# Carrier_Board.net
KiCad netlist of a schematic drawn in EAGLE
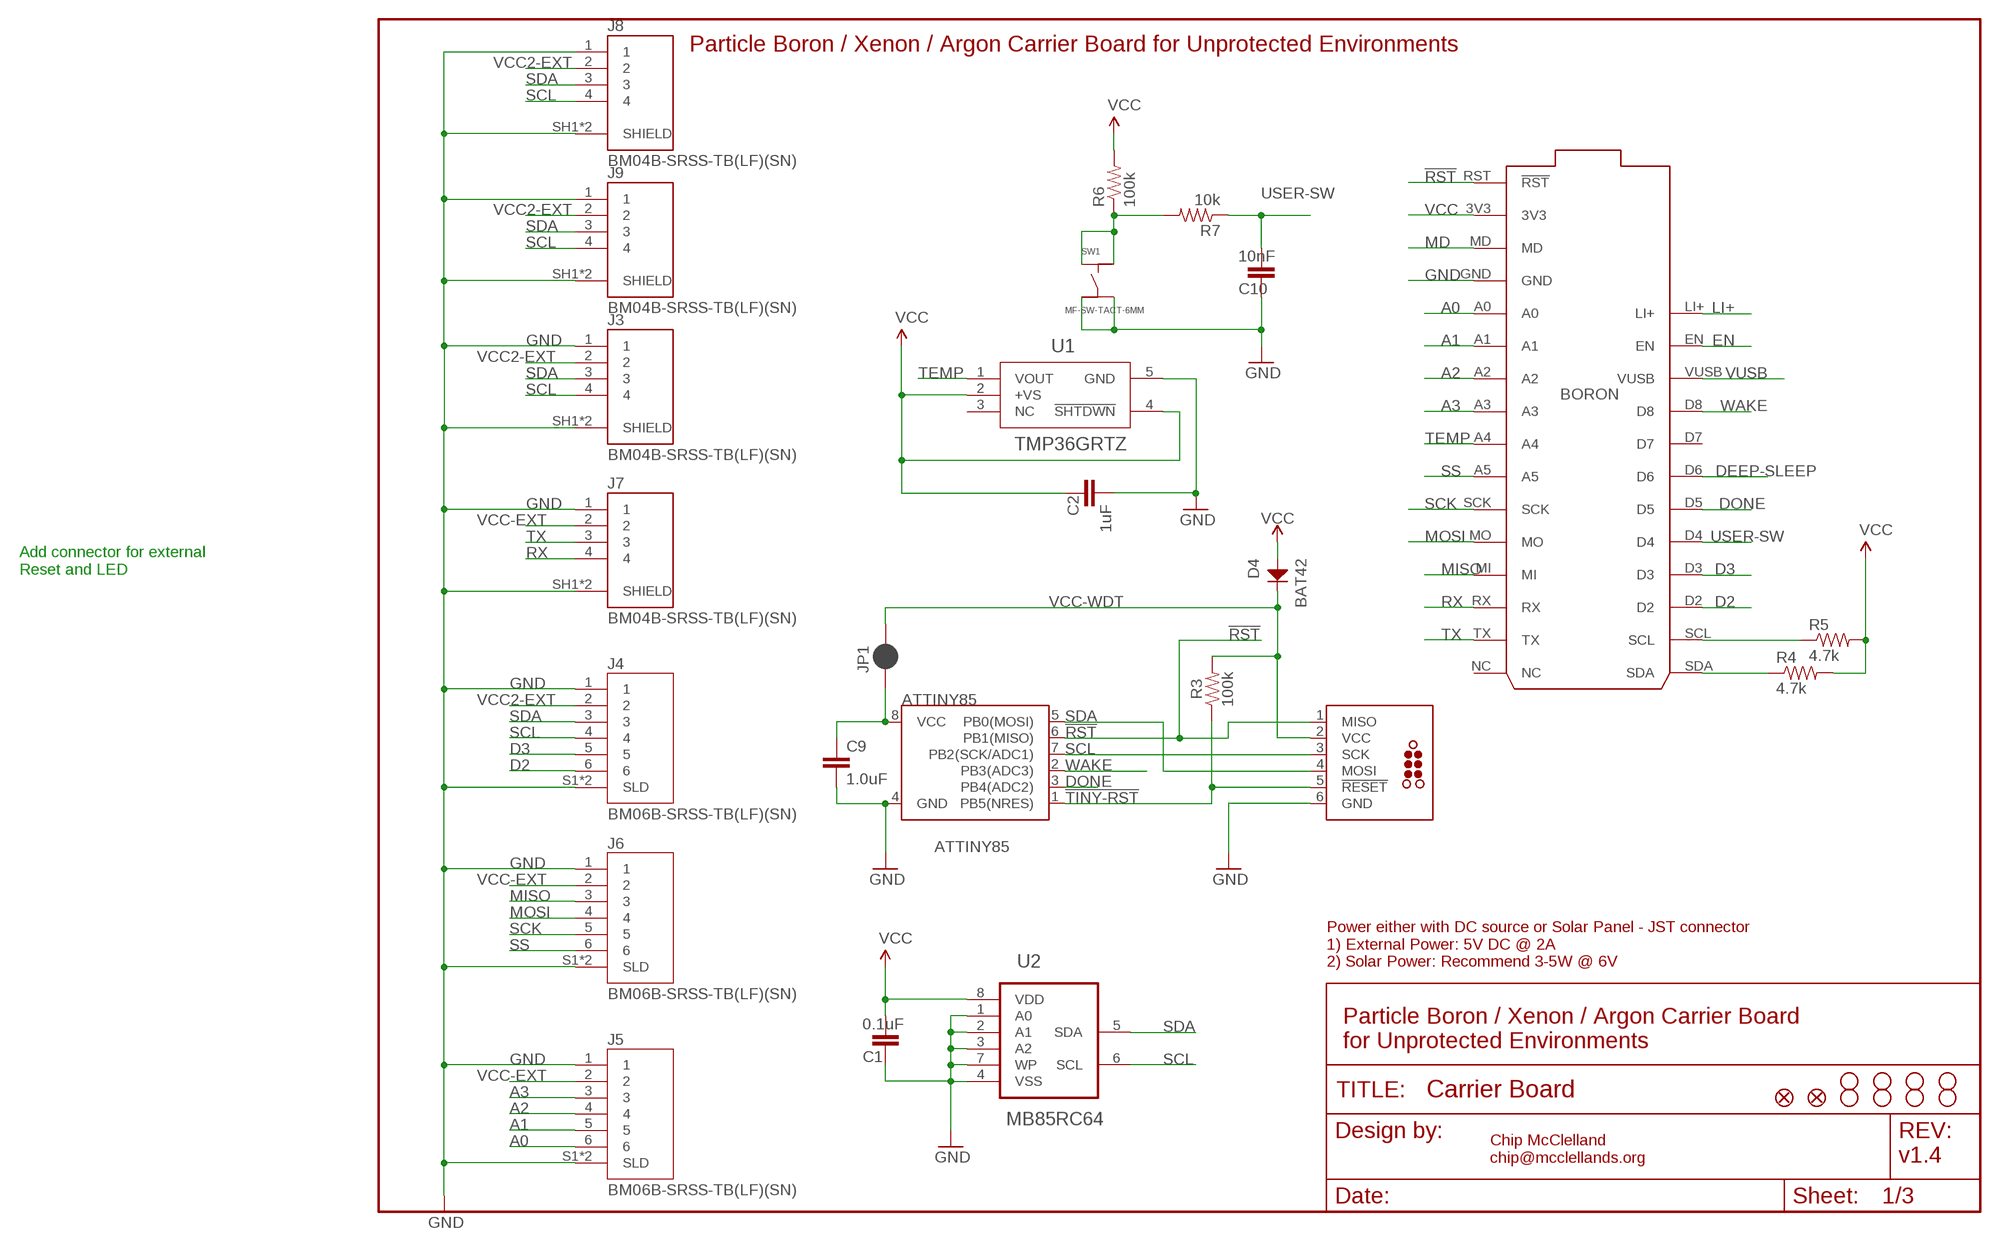
[diagram p0: schematic, sheet 1]
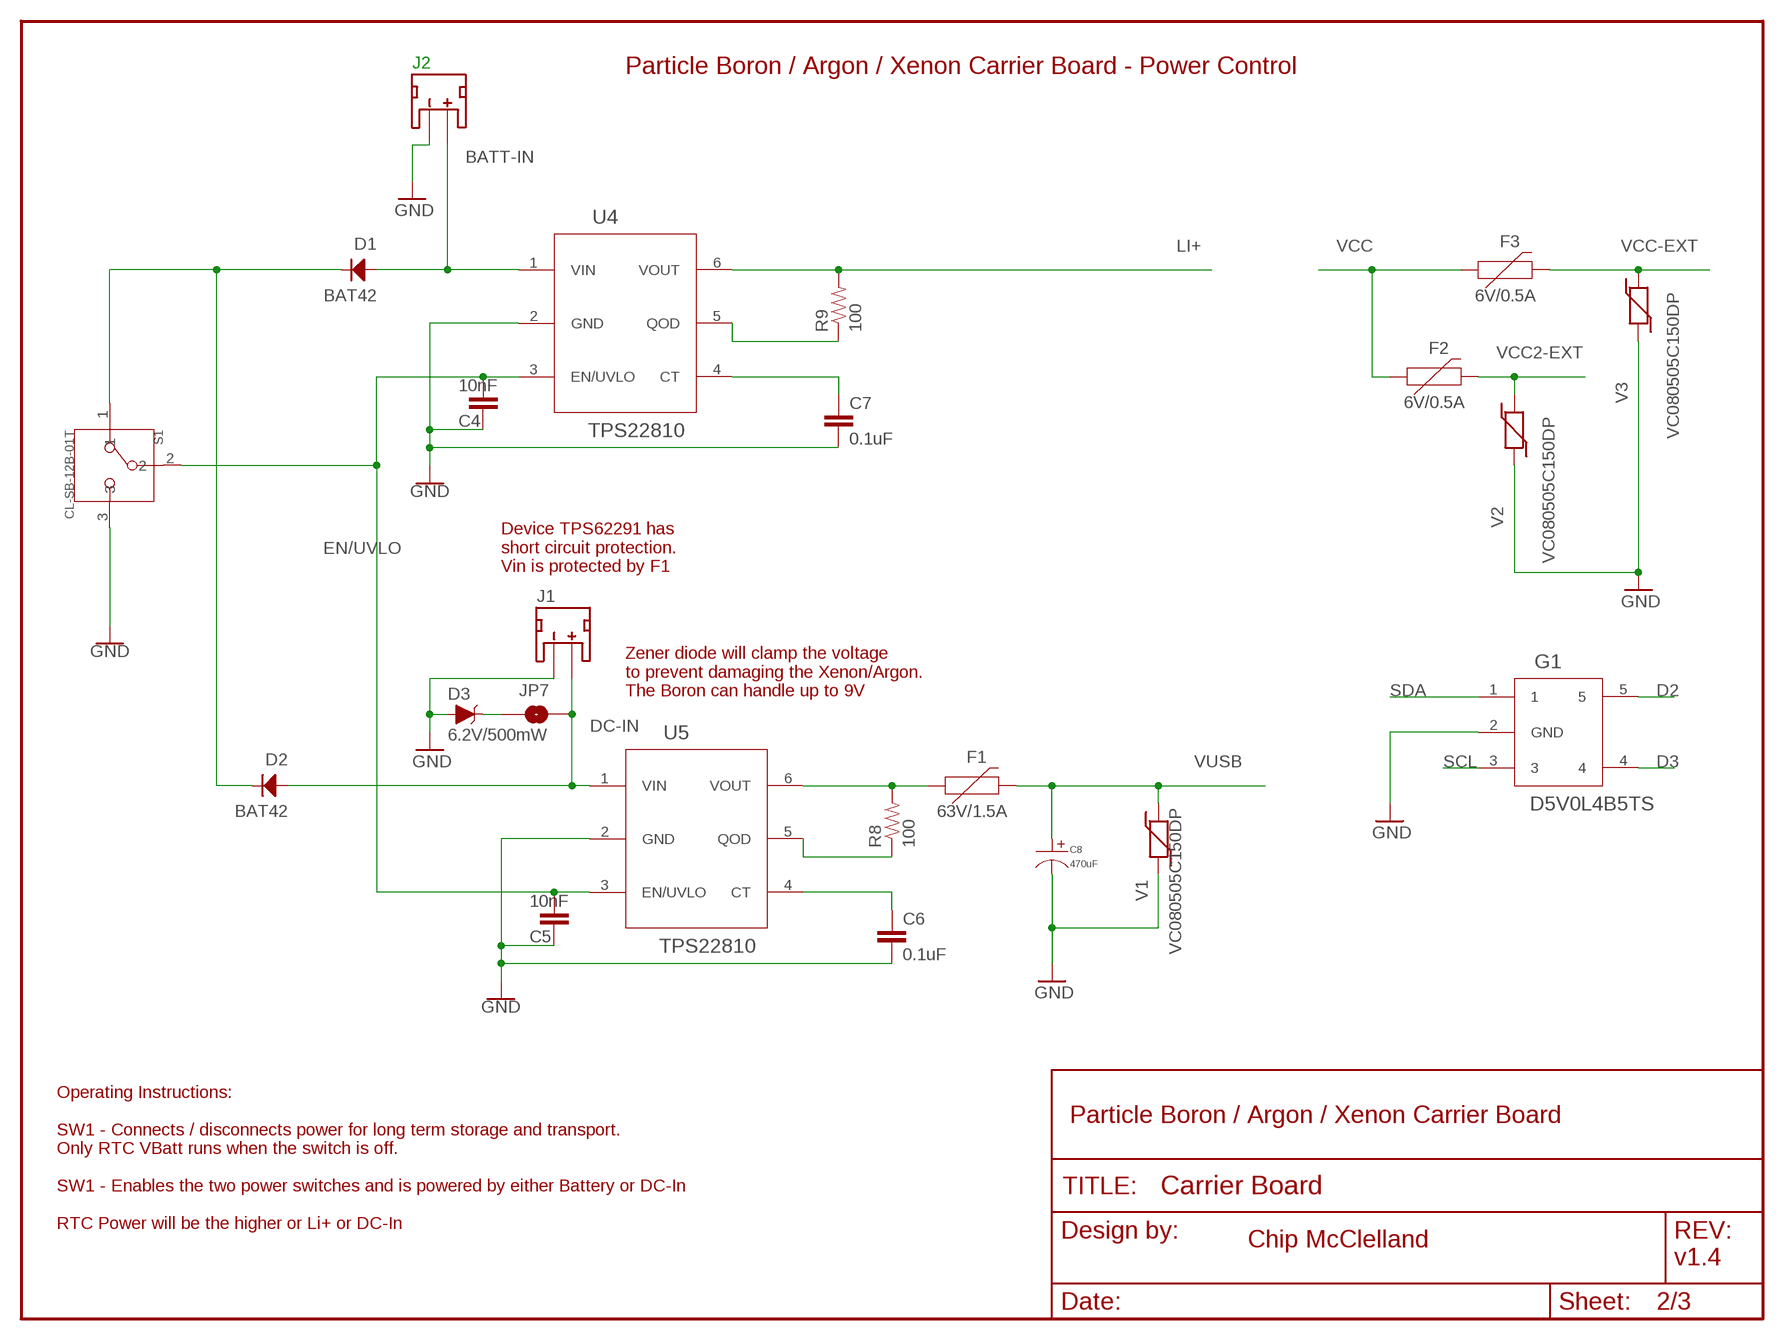
[diagram p1: schematic, sheet 2]
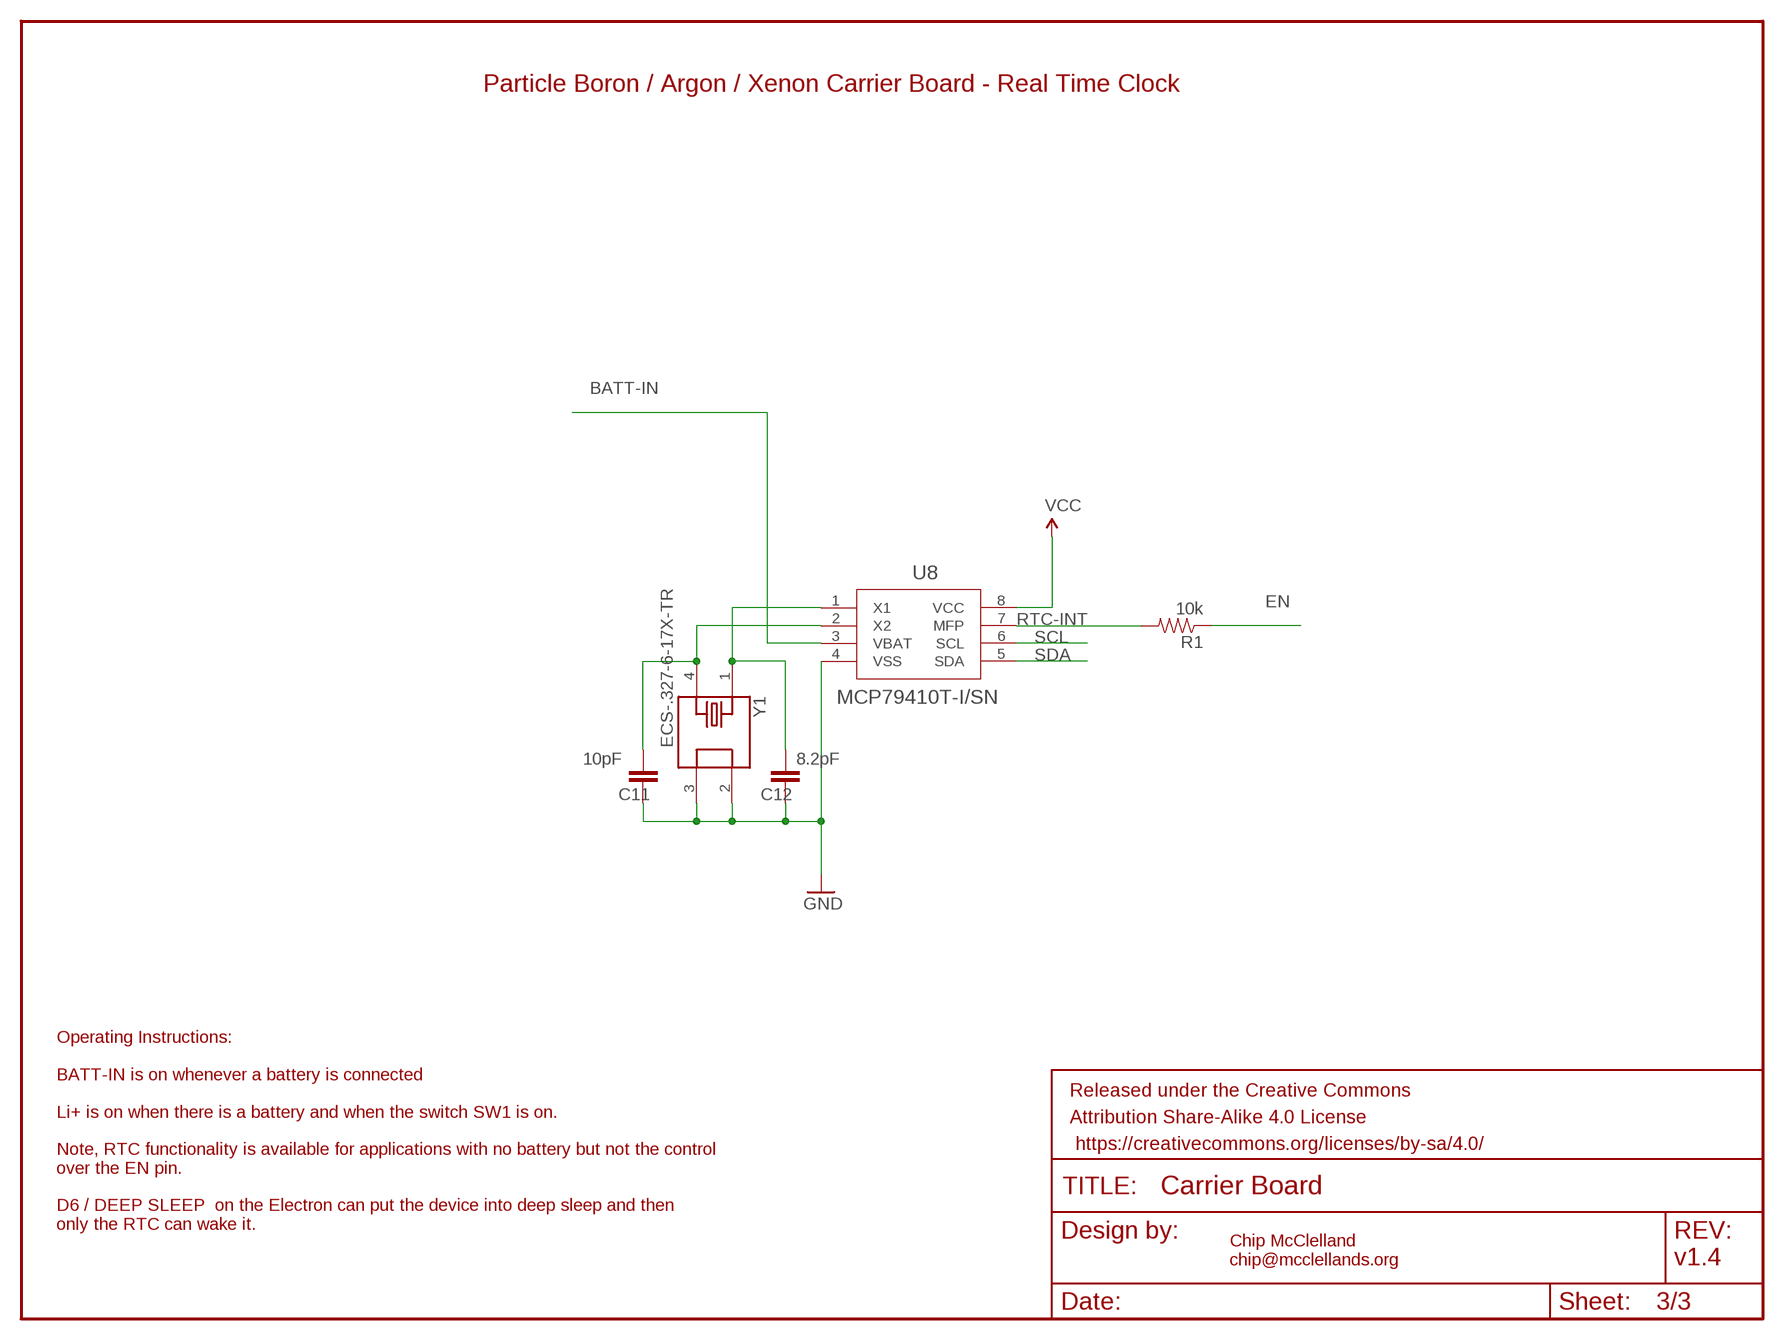
[diagram p2: schematic, sheet 3]

(export (version "E")
  (design (tool "Eeschema 10.0.6"))
  (components
    (comp (ref "ATTINY85")
      (value "ATTINY85")
      (footprint "eagle-import:SO08-EIAJ")
      (fields (field (name "MPN") "ATTINY85-20SUR"))
      (libsource (lib "eagle-import") (part "ATTINY45"))
    )
    (comp (ref "C1")
      (value "0.1uF")
      (footprint "eagle-import:0805@1")
      (fields (field (name "HOUSEPART") "YES") (field (name "MPN") "MF-CAP-0805-0.1uF"))
      (libsource (lib "eagle-import") (part "CAP0805"))
    )
    (comp (ref "C2")
      (value "1uF")
      (footprint "eagle-import:0805@1")
      (fields (field (name "MPN") "MF-CAP-0805-1uF"))
      (libsource (lib "eagle-import") (part "CAP0805"))
    )
    (comp (ref "C9")
      (value "1.0uF")
      (footprint "eagle-import:0805")
      (fields (field (name "MPN") "MF-CAP-0805-0.1uF"))
      (libsource (lib "eagle-import") (part "1.0UF-0805-25V-10%"))
    )
    (comp (ref "C10")
      (value "10nF")
      (footprint "eagle-import:0805@1")
      (fields (field (name "HOUSEPART") "No") (field (name "MPN") "08051C103K4T2A"))
      (libsource (lib "eagle-import") (part "CAP0805"))
    )
    (comp (ref "D4")
      (value "BAT42")
      (footprint "eagle-import:SOD-123")
      (fields (field (name "HOUSEPART") "YES") (field (name "MPN") "MF-DIO-SOD123-BAT42"))
      (libsource (lib "eagle-import") (part "DIODES_SOD-123_BAT42"))
    )
    (comp (ref "FD1")
      (value "FIDUCIALUFIDUCIAL")
      (footprint "eagle-import:FIDUCIAL-MICRO")
      (libsource (lib "eagle-import") (part "FIDUCIALUFIDUCIAL"))
    )
    (comp (ref "FD2")
      (value "FIDUCIALUFIDUCIAL")
      (footprint "eagle-import:FIDUCIAL-MICRO")
      (libsource (lib "eagle-import") (part "FIDUCIALUFIDUCIAL"))
    )
    (comp (ref "FRAME1")
      (value "FRAME-LETTER")
      (footprint "eagle-import:CREATIVE_COMMONS")
      (fields (field (name "POPULATE") "0"))
      (libsource (lib "eagle-import") (part "FRAME-LETTER"))
    )
    (comp (ref "H1")
      (value "STAND-OFF-M2.5")
      (footprint "eagle-import:STAND-OFF-M2.5")
      (libsource (lib "eagle-import") (part "STAND-OFF-M2.5"))
    )
    (comp (ref "H2")
      (value "STAND-OFF-M2.5")
      (footprint "eagle-import:STAND-OFF-M2.5")
      (libsource (lib "eagle-import") (part "STAND-OFF-M2.5"))
    )
    (comp (ref "H3")
      (value "STAND-OFF-M2.5")
      (footprint "eagle-import:STAND-OFF-M2.5")
      (libsource (lib "eagle-import") (part "STAND-OFF-M2.5"))
    )
    (comp (ref "H4")
      (value "STAND-OFF-M2.5")
      (footprint "eagle-import:STAND-OFF-M2.5")
      (libsource (lib "eagle-import") (part "STAND-OFF-M2.5"))
    )
    (comp (ref "ICSP")
      (value "TCP2030-MCP-NL")
      (footprint "eagle-import:TC2030-MCP-NL")
      (libsource (lib "eagle-import") (part "TCP2030-MCP-NL"))
    )
    (comp (ref "J3")
      (value "BM04B-SRSS-TB(LF)(SN)")
      (footprint "eagle-import:CONN_BM04B-SRSS-TBT(LF)(SN)")
      (fields (field (name "MF") "JST Sales") (field (name "MP") "BM04B-SRSS-TB_LF__SN_"))
      (libsource (lib "eagle-import") (part "BM04B-SRSS-TBT(LF)(SN)"))
    )
    (comp (ref "J4")
      (value "BM06B-SRSS-TB(LF)(SN)")
      (footprint "eagle-import:JST_BM06B-SRSS-TB(LF)(SN)")
      (libsource (lib "eagle-import") (part "BM06B-SRSS-TB(LF)(SN)"))
    )
    (comp (ref "J5")
      (value "BM06B-SRSS-TB(LF)(SN)")
      (footprint "eagle-import:JST_BM06B-SRSS-TB(LF)(SN)")
      (libsource (lib "eagle-import") (part "BM06B-SRSS-TB(LF)(SN)"))
    )
    (comp (ref "J6")
      (value "BM06B-SRSS-TB(LF)(SN)")
      (footprint "eagle-import:JST_BM06B-SRSS-TB(LF)(SN)")
      (libsource (lib "eagle-import") (part "BM06B-SRSS-TB(LF)(SN)"))
    )
    (comp (ref "J7")
      (value "BM04B-SRSS-TB(LF)(SN)")
      (footprint "eagle-import:CONN_BM04B-SRSS-TBT(LF)(SN)")
      (fields (field (name "MF") "JST Sales") (field (name "MP") "BM04B-SRSS-TB_LF__SN_"))
      (libsource (lib "eagle-import") (part "BM04B-SRSS-TBT(LF)(SN)"))
    )
    (comp (ref "J8")
      (value "BM04B-SRSS-TB(LF)(SN)")
      (footprint "eagle-import:CONN_BM04B-SRSS-TBT(LF)(SN)")
      (fields (field (name "MF") "JST Sales") (field (name "MP") "BM04B-SRSS-TB_LF__SN_"))
      (libsource (lib "eagle-import") (part "BM04B-SRSS-TBT(LF)(SN)"))
    )
    (comp (ref "J9")
      (value "BM04B-SRSS-TB(LF)(SN)")
      (footprint "eagle-import:CONN_BM04B-SRSS-TBT(LF)(SN)")
      (fields (field (name "MF") "JST Sales") (field (name "MP") "BM04B-SRSS-TB_LF__SN_"))
      (libsource (lib "eagle-import") (part "BM04B-SRSS-TBT(LF)(SN)"))
    )
    (comp (ref "JP1")
      (value "JUMPER-SMT_2_NC_PASTE_SILK")
      (footprint "eagle-import:SMT-JUMPER_2_NC_PASTE_SILK")
      (libsource (lib "eagle-import") (part "JUMPER-SMT_2_NC_PASTE_SILK"))
    )
    (comp (ref "JP3")
      (value "STAND-OFF")
      (footprint "eagle-import:STAND-OFF")
      (libsource (lib "eagle-import") (part "STAND-OFF"))
    )
    (comp (ref "JP4")
      (value "STAND-OFF")
      (footprint "eagle-import:STAND-OFF")
      (libsource (lib "eagle-import") (part "STAND-OFF"))
    )
    (comp (ref "JP5")
      (value "STAND-OFF")
      (footprint "eagle-import:STAND-OFF")
      (libsource (lib "eagle-import") (part "STAND-OFF"))
    )
    (comp (ref "JP6")
      (value "STAND-OFF")
      (footprint "eagle-import:STAND-OFF")
      (libsource (lib "eagle-import") (part "STAND-OFF"))
    )
    (comp (ref "P1")
      (value "Particle Boron / Xenon / Argon")
      (footprint "eagle-import:PARTICLE-DEVICES_BORON")
      (libsource (lib "eagle-import") (part "PARTICLE-DEVICES-BORON"))
    )
    (comp (ref "R3")
      (value "100k")
      (footprint "eagle-import:0805")
      (fields (field (name "MPN") "MF-RES-0805-100K"))
      (libsource (lib "eagle-import") (part "0.3OHM-0805-1/8W-1%"))
    )
    (comp (ref "R4")
      (value "4.7k")
      (footprint "eagle-import:0805")
      (fields (field (name "MPN") "MF-RES-0805-4.7K"))
      (libsource (lib "eagle-import") (part "RESISTOR0805-RES"))
    )
    (comp (ref "R5")
      (value "4.7k")
      (footprint "eagle-import:0805")
      (fields (field (name "MPN") "MF-RES-0805-4.7K"))
      (libsource (lib "eagle-import") (part "RESISTOR0805-RES"))
    )
    (comp (ref "R6")
      (value "100k")
      (footprint "eagle-import:0805")
      (fields (field (name "HOUSEPART") "YES") (field (name "MPN") "MF-RES-0805-100K"))
      (libsource (lib "eagle-import") (part "RESISTOR0805-RES"))
    )
    (comp (ref "R7")
      (value "10k")
      (footprint "eagle-import:0805")
      (fields (field (name "HOUSEPART") "YES") (field (name "MPN") "MF-RES-0805-10K"))
      (libsource (lib "eagle-import") (part "RESISTOR0805-RES"))
    )
    (comp (ref "SW1")
      (value "MF-SW-TACT-6MM")
      (footprint "eagle-import:TACT6MM")
      (fields (field (name "HOUSEPART") "YES"))
      (libsource (lib "eagle-import") (part "TACT_6MM"))
    )
    (comp (ref "U1")
      (value "TMP36GRTZ")
      (footprint "eagle-import:RJ_5")
      (fields
        (field (name "MANUFACTURER_PART_NUMBER") "TMP36GRTZREEL7")
        (field (name "MANUFACTURER_PART_NUMBER_1") "TMP36GRTZ-REEL7")
        (field (name "MPN") "TMP36GRTZ-REEL7")
      )
      (libsource (lib "eagle-import") (part "TMP36GRTZ-REEL7"))
    )
    (comp (ref "U2")
      (value "MB85RC64")
      (footprint "eagle-import:SOIC127P600X175-8N")
      (fields (field (name "MPN") "MB85RC128PNF-G-JNE1") (field (name "MPN_1") "MB85RC64APNF-G-JNERE1"))
      (libsource (lib "eagle-import") (part "MB85RC128PNF-G-JNE1"))
    )
    (comp (ref "C11")
      (value "10pF")
      (footprint "eagle-import:0805@1")
      (fields (field (name "HOUSEPART") "No") (field (name "MPN") "C0805C100JDGACTU‎"))
      (libsource (lib "eagle-import") (part "CAP0805"))
    )
    (comp (ref "C12")
      (value "8.2pF")
      (footprint "eagle-import:0805@1")
      (fields (field (name "HOUSEPART") "No") (field (name "MPN") "C0805C829D5GACTU‎"))
      (libsource (lib "eagle-import") (part "CAP0805"))
    )
    (comp (ref "FRAME3")
      (value "FRAME-LETTER")
      (footprint "eagle-import:CREATIVE_COMMONS")
      (fields (field (name "POPULATE") "0"))
      (libsource (lib "eagle-import") (part "SparkFun-Aesthetics_507_FRAME-LETTER"))
    )
    (comp (ref "R1")
      (value "10k")
      (footprint "eagle-import:0805")
      (fields (field (name "HOUSEPART") "YES") (field (name "MPN") "MF-RES-0805-10K"))
      (libsource (lib "eagle-import") (part "RESISTOR0805-RES"))
    )
    (comp (ref "U8")
      (value "MCP79410T-I/SN")
      (footprint "eagle-import:SOIC8-N_MC")
      (fields (field (name "MANUFACTURER_PART_NUMBER") "MCP79410TISN"))
      (libsource (lib "eagle-import") (part "MCP79410T-I/SN"))
    )
    (comp (ref "Y1")
      (value "ECS-.327-6-17X-TR")
      (footprint "eagle-import:XTAL_ECS-.327-6-17X-TR")
      (fields (field (name "DIGI-KEY_PART_NUMBER") "XC1307CT-ND") (field (name "MF") "ECS Inc."))
      (libsource (lib "eagle-import") (part "ECS-.327-6-17X-TR"))
    )
    (comp (ref "C4")
      (value "10nF")
      (footprint "eagle-import:0805@1")
      (fields (field (name "HOUSEPART") "No") (field (name "MPN") "08051C103K4T2A"))
      (libsource (lib "eagle-import") (part "CAP0805"))
    )
    (comp (ref "C5")
      (value "10nF")
      (footprint "eagle-import:0805@1")
      (fields (field (name "HOUSEPART") "No") (field (name "MPN") "08051C103K4T2A"))
      (libsource (lib "eagle-import") (part "CAP0805"))
    )
    (comp (ref "C6")
      (value "0.1uF")
      (footprint "eagle-import:0805@1")
      (fields (field (name "HOUSEPART") "Yes") (field (name "MPN") "MF-CAP-0805-0.1uF"))
      (libsource (lib "eagle-import") (part "CAP0805"))
    )
    (comp (ref "C7")
      (value "0.1uF")
      (footprint "eagle-import:0805@1")
      (fields (field (name "HOUSEPART") "Yes") (field (name "MPN") "MF-CAP-0805-0.1uF"))
      (libsource (lib "eagle-import") (part "CAP0805"))
    )
    (comp (ref "C8")
      (value "470uF")
      (footprint "eagle-import:CP10MM")
      (fields (field (name "HOUSEPART") "1") (field (name "MPN") "MF-CAP-10MM-470uF"))
      (libsource (lib "eagle-import") (part "CAPACITOR_P_10MM"))
    )
    (comp (ref "D1")
      (value "BAT42")
      (footprint "eagle-import:SOD-123")
      (fields (field (name "HOUSEPART") "YES") (field (name "MPN") "MF-DIO-SOD123-BAT42"))
      (libsource (lib "eagle-import") (part "DIODES_SOD-123_BAT42"))
    )
    (comp (ref "D2")
      (value "BAT42")
      (footprint "eagle-import:SOD-123")
      (fields (field (name "HOUSEPART") "YES") (field (name "MPN") "MF-DIO-SOD123-BAT42"))
      (libsource (lib "eagle-import") (part "DIODES_SOD-123_BAT42"))
    )
    (comp (ref "D3")
      (value "6.2V/500mW")
      (footprint "eagle-import:PANASONIC_SMINI2-F5-B")
      (fields (field (name "MPN") "TDZ6V2J,115"))
      (libsource (lib "eagle-import") (part "DIODE-ZENER-DZ2J150M0L"))
    )
    (comp (ref "F1")
      (value "63V/1.5A")
      (footprint "eagle-import:1206")
      (fields (field (name "MPN") "046801.5NR"))
      (libsource (lib "eagle-import") (part "PPTC_HALF-AMP"))
    )
    (comp (ref "F2")
      (value "6V/0.5A")
      (footprint "eagle-import:1206")
      (fields (field (name "MPN") "0466.500NR"))
      (libsource (lib "eagle-import") (part "PPTC_HALF-AMP"))
    )
    (comp (ref "F3")
      (value "6V/0.5A")
      (footprint "eagle-import:1206")
      (fields (field (name "MPN") "0466.500NR"))
      (libsource (lib "eagle-import") (part "PPTC_HALF-AMP"))
    )
    (comp (ref "FRAME2")
      (value "FRAME-LETTER")
      (footprint "eagle-import:CREATIVE_COMMONS")
      (fields (field (name "POPULATE") "0"))
      (libsource (lib "eagle-import") (part "FRAME-LETTER"))
    )
    (comp (ref "G1")
      (value "D5V0L4B5TS")
      (footprint "eagle-import:SOT-23-5")
      (fields (field (name "MPN") "D5V0L4B5TS-7"))
      (libsource (lib "eagle-import") (part "D5V0L4B5TS"))
    )
    (comp (ref "J1")
      (value "S2B-PH-SM4-TB(LF)(SN)")
      (footprint "eagle-import:JST-2-SMD")
      (fields (field (name "MFG") "JST S2B-PH-SM4-TB(LF)(SN)"))
      (libsource (lib "eagle-import") (part "JST_2MM_MALE"))
    )
    (comp (ref "J2")
      (value "S2B-PH-SM4-TB(LF)(SN)")
      (footprint "eagle-import:JST-2-SMD")
      (fields (field (name "MFG") "JST S2B-PH-SM4-TB(LF)(SN)"))
      (libsource (lib "eagle-import") (part "JST_2MM_MALE"))
    )
    (comp (ref "JP7")
      (value "JUMPER-SMT_2_NO_SILK")
      (footprint "eagle-import:SMT-JUMPER_2_NO_SILK")
      (libsource (lib "eagle-import") (part "JUMPER-SMT_2_NO_SILK"))
    )
    (comp (ref "R8")
      (value "100")
      (footprint "eagle-import:0805")
      (fields (field (name "HOUSEPART") "Yes") (field (name "MPN") "MF-RES-0805-100"))
      (libsource (lib "eagle-import") (part "RESISTOR0805-RES"))
    )
    (comp (ref "R9")
      (value "100")
      (footprint "eagle-import:0805")
      (fields (field (name "HOUSEPART") "Yes") (field (name "MPN") "MF-RES-0805-100"))
      (libsource (lib "eagle-import") (part "RESISTOR0805-RES"))
    )
    (comp (ref "S1")
      (value "CL-SB-12B-01T")
      (footprint "eagle-import:CL-SB-12B")
      (fields (field (name "DIGI-KEY_PART_NUMBER") "563-1318-1-ND") (field (name "MF") "Nidec Copal"))
      (libsource (lib "eagle-import") (part "CL-SB-12B-01T"))
    )
    (comp (ref "U4")
      (value "TPS22810")
      (footprint "eagle-import:SOT-23-6")
      (fields (field (name "MPN") "TPS22810DBVT"))
      (libsource (lib "eagle-import") (part "TPS22810"))
    )
    (comp (ref "U5")
      (value "TPS22810")
      (footprint "eagle-import:SOT-23-6")
      (fields (field (name "MPN") "TPS22810DBVT"))
      (libsource (lib "eagle-import") (part "TPS22810"))
    )
    (comp (ref "V1")
      (value "VC080505C150DP")
      (footprint "eagle-import:0805")
      (libsource (lib "eagle-import") (part "VARISTOR"))
    )
    (comp (ref "V2")
      (value "VC080505C150DP")
      (footprint "eagle-import:0805")
      (libsource (lib "eagle-import") (part "VARISTOR"))
    )
    (comp (ref "V3")
      (value "VC080505C150DP")
      (footprint "eagle-import:0805")
      (libsource (lib "eagle-import") (part "VARISTOR"))
    )
  )
  (nets
    (net (code "1") (name "A0") (class "Default")
      (node (ref "J5") (pin "6") (pinfunction "6_6") (pintype "passive"))
      (node (ref "P1") (pin "A0") (pinfunction "A0_A0") (pintype "bidirectional"))
    )
    (net (code "2") (name "A1") (class "Default")
      (node (ref "J5") (pin "5") (pinfunction "5_5") (pintype "passive"))
      (node (ref "P1") (pin "A1") (pinfunction "A1_A1") (pintype "bidirectional"))
    )
    (net (code "3") (name "A2") (class "Default")
      (node (ref "J5") (pin "4") (pinfunction "4_4") (pintype "passive"))
      (node (ref "P1") (pin "A2") (pinfunction "A2_A2") (pintype "bidirectional"))
    )
    (net (code "4") (name "A3") (class "Default")
      (node (ref "J5") (pin "3") (pinfunction "3_3") (pintype "passive"))
      (node (ref "P1") (pin "A3") (pinfunction "A3_A3") (pintype "bidirectional"))
    )
    (net (code "5") (name "BATT-IN") (class "Default")
      (node (ref "D1") (pin "ANODE") (pinfunction "ANODE_ANODE") (pintype "bidirectional"))
      (node (ref "J2") (pin "2") (pinfunction "+_2") (pintype "bidirectional"))
      (node (ref "U4") (pin "1") (pinfunction "VIN_1") (pintype "power_in"))
      (node (ref "U8") (pin "3") (pinfunction "VBAT_3") (pintype "input"))
    )
    (net (code "6") (name "D2") (class "Default")
      (node (ref "G1") (pin "5") (pinfunction "5_5") (pintype "output"))
      (node (ref "J4") (pin "6") (pinfunction "6_6") (pintype "passive"))
      (node (ref "P1") (pin "D2") (pinfunction "D2_D2") (pintype "bidirectional"))
    )
    (net (code "7") (name "D3") (class "Default")
      (node (ref "G1") (pin "4") (pinfunction "4_4") (pintype "output"))
      (node (ref "J4") (pin "5") (pinfunction "5_5") (pintype "passive"))
      (node (ref "P1") (pin "D3") (pinfunction "D3_D3") (pintype "bidirectional"))
    )
    (net (code "8") (name "DC-IN") (class "Default")
      (node (ref "D2") (pin "ANODE") (pinfunction "ANODE_ANODE") (pintype "bidirectional"))
      (node (ref "J1") (pin "2") (pinfunction "+_2") (pintype "bidirectional"))
      (node (ref "JP7") (pin "1") (pinfunction "1_1") (pintype "passive"))
      (node (ref "U5") (pin "1") (pinfunction "VIN_1") (pintype "power_in"))
    )
    (net (code "9") (name "DEEP-SLEEP") (class "Default")
      (node (ref "P1") (pin "D6") (pinfunction "D6_D6") (pintype "bidirectional"))
    )
    (net (code "10") (name "DONE") (class "Default")
      (node (ref "ATTINY85") (pin "3") (pinfunction "PB4(ADC2)_3") (pintype "bidirectional"))
      (node (ref "P1") (pin "D5") (pinfunction "D5_D5") (pintype "bidirectional"))
    )
    (net (code "11") (name "EN") (class "Default")
      (node (ref "P1") (pin "EN") (pinfunction "EN_EN") (pintype "bidirectional"))
      (node (ref "R1") (pin "1") (pinfunction "1_1") (pintype "passive"))
    )
    (net (code "12") (name "EN{slash}UVLO") (class "Default")
      (node (ref "C4") (pin "1") (pinfunction "1_1") (pintype "passive"))
      (node (ref "C5") (pin "1") (pinfunction "1_1") (pintype "passive"))
      (node (ref "S1") (pin "2") (pinfunction "2_2") (pintype "bidirectional"))
      (node (ref "U4") (pin "3") (pinfunction "EN/UVLO_3") (pintype "input"))
      (node (ref "U5") (pin "3") (pinfunction "EN/UVLO_3") (pintype "input"))
    )
    (net (code "13") (name "GND") (class "Default")
      (node (ref "ATTINY85") (pin "4") (pinfunction "GND_4") (pintype "bidirectional"))
      (node (ref "C1") (pin "2") (pinfunction "2_2") (pintype "passive"))
      (node (ref "C10") (pin "2") (pinfunction "2_2") (pintype "passive"))
      (node (ref "C11") (pin "2") (pinfunction "2_2") (pintype "passive"))
      (node (ref "C12") (pin "2") (pinfunction "2_2") (pintype "passive"))
      (node (ref "C2") (pin "2") (pinfunction "2_2") (pintype "passive"))
      (node (ref "C4") (pin "2") (pinfunction "2_2") (pintype "passive"))
      (node (ref "C5") (pin "2") (pinfunction "2_2") (pintype "passive"))
      (node (ref "C6") (pin "2") (pinfunction "2_2") (pintype "passive"))
      (node (ref "C7") (pin "2") (pinfunction "2_2") (pintype "passive"))
      (node (ref "C8") (pin "P$2") (pinfunction "P$2_P$2") (pintype "passive"))
      (node (ref "C9") (pin "2") (pinfunction "2_2") (pintype "passive"))
      (node (ref "D3") (pin "A") (pinfunction "A_A") (pintype "passive"))
      (node (ref "G1") (pin "2") (pinfunction "GND_2") (pintype "power_in"))
      (node (ref "ICSP") (pin "6") (pinfunction "GND_6") (pintype "power_in"))
      (node (ref "J1") (pin "1") (pinfunction "-_1") (pintype "bidirectional"))
      (node (ref "J2") (pin "1") (pinfunction "-_1") (pintype "bidirectional"))
      (node (ref "J3") (pin "1") (pinfunction "1_1") (pintype "passive"))
      (node (ref "J3") (pin "SH1") (pinfunction "SHIELD_SH1") (pintype "passive"))
      (node (ref "J3") (pin "SH2") (pinfunction "SHIELD_SH2") (pintype "passive"))
      (node (ref "J4") (pin "1") (pinfunction "1_1") (pintype "passive"))
      (node (ref "J4") (pin "S1") (pinfunction "SLD_S1") (pintype "passive"))
      (node (ref "J4") (pin "S2") (pinfunction "SLD_S2") (pintype "passive"))
      (node (ref "J5") (pin "1") (pinfunction "1_1") (pintype "passive"))
      (node (ref "J5") (pin "S1") (pinfunction "SLD_S1") (pintype "passive"))
      (node (ref "J5") (pin "S2") (pinfunction "SLD_S2") (pintype "passive"))
      (node (ref "J6") (pin "1") (pinfunction "1_1") (pintype "passive"))
      (node (ref "J6") (pin "S1") (pinfunction "SLD_S1") (pintype "passive"))
      (node (ref "J6") (pin "S2") (pinfunction "SLD_S2") (pintype "passive"))
      (node (ref "J7") (pin "1") (pinfunction "1_1") (pintype "passive"))
      (node (ref "J7") (pin "SH1") (pinfunction "SHIELD_SH1") (pintype "passive"))
      (node (ref "J7") (pin "SH2") (pinfunction "SHIELD_SH2") (pintype "passive"))
      (node (ref "J8") (pin "1") (pinfunction "1_1") (pintype "passive"))
      (node (ref "J8") (pin "SH1") (pinfunction "SHIELD_SH1") (pintype "passive"))
      (node (ref "J8") (pin "SH2") (pinfunction "SHIELD_SH2") (pintype "passive"))
      (node (ref "J9") (pin "1") (pinfunction "1_1") (pintype "passive"))
      (node (ref "J9") (pin "SH1") (pinfunction "SHIELD_SH1") (pintype "passive"))
      (node (ref "J9") (pin "SH2") (pinfunction "SHIELD_SH2") (pintype "passive"))
      (node (ref "P1") (pin "GND") (pinfunction "GND_GND") (pintype "bidirectional"))
      (node (ref "S1") (pin "3") (pinfunction "3_3") (pintype "bidirectional"))
      (node (ref "SW1") (pin "P$3") (pinfunction "P$3_P$3") (pintype "bidirectional"))
      (node (ref "SW1") (pin "P$4") (pinfunction "P$4_P$4") (pintype "bidirectional"))
      (node (ref "U1") (pin "5") (pinfunction "GND_5") (pintype "passive"))
      (node (ref "U2") (pin "1") (pinfunction "A0_1") (pintype "input"))
      (node (ref "U2") (pin "2") (pinfunction "A1_2") (pintype "input"))
      (node (ref "U2") (pin "3") (pinfunction "A2_3") (pintype "input"))
      (node (ref "U2") (pin "4") (pinfunction "VSS_4") (pintype "passive"))
      (node (ref "U2") (pin "7") (pinfunction "WP_7") (pintype "input"))
      (node (ref "U4") (pin "2") (pinfunction "GND_2") (pintype "power_in"))
      (node (ref "U5") (pin "2") (pinfunction "GND_2") (pintype "power_in"))
      (node (ref "U8") (pin "4") (pinfunction "VSS_4") (pintype "power_in"))
      (node (ref "V1") (pin "1") (pinfunction "1_1") (pintype "passive"))
      (node (ref "V2") (pin "1") (pinfunction "1_1") (pintype "passive"))
      (node (ref "V3") (pin "1") (pinfunction "1_1") (pintype "passive"))
      (node (ref "Y1") (pin "2") (pinfunction "2_2") (pintype "passive"))
      (node (ref "Y1") (pin "3") (pinfunction "3_3") (pintype "passive"))
    )
    (net (code "14") (name "LI+") (class "Default")
      (node (ref "P1") (pin "LI+") (pinfunction "LI+_LI+") (pintype "bidirectional"))
      (node (ref "R9") (pin "2") (pinfunction "2_2") (pintype "passive"))
      (node (ref "U4") (pin "6") (pinfunction "VOUT_6") (pintype "power_in"))
    )
    (net (code "15") (name "MD") (class "Default")
      (node (ref "P1") (pin "MD") (pinfunction "MD_MD") (pintype "bidirectional"))
    )
    (net (code "16") (name "MISO") (class "Default")
      (node (ref "J6") (pin "3") (pinfunction "3_3") (pintype "passive"))
      (node (ref "P1") (pin "MI") (pinfunction "MI_MI") (pintype "bidirectional"))
    )
    (net (code "17") (name "MOSI") (class "Default")
      (node (ref "J6") (pin "4") (pinfunction "4_4") (pintype "passive"))
      (node (ref "P1") (pin "MO") (pinfunction "MO_MO") (pintype "bidirectional"))
    )
    (net (code "18") (name "Net-(ATTINY85-VCC)") (class "Default")
      (node (ref "ATTINY85") (pin "8") (pinfunction "VCC_8") (pintype "bidirectional"))
      (node (ref "C9") (pin "1") (pinfunction "1_1") (pintype "passive"))
      (node (ref "JP1") (pin "1") (pinfunction "1_1") (pintype "passive"))
    )
    (net (code "19") (name "Net-(D1-PadCATHODE)") (class "Default")
      (node (ref "D1") (pin "CATHODE") (pinfunction "CATHODE_CATHODE") (pintype "bidirectional"))
      (node (ref "D2") (pin "CATHODE") (pinfunction "CATHODE_CATHODE") (pintype "bidirectional"))
      (node (ref "S1") (pin "1") (pinfunction "1_1") (pintype "bidirectional"))
    )
    (net (code "20") (name "Net-(D3-PadC)") (class "Default")
      (node (ref "D3") (pin "C") (pinfunction "C_C") (pintype "passive"))
      (node (ref "JP7") (pin "2") (pinfunction "2_2") (pintype "passive"))
    )
    (net (code "21") (name "Net-(R6-Pad1)") (class "Default")
      (node (ref "R6") (pin "1") (pinfunction "1_1") (pintype "passive"))
      (node (ref "R7") (pin "2") (pinfunction "2_2") (pintype "passive"))
      (node (ref "SW1") (pin "P$1") (pinfunction "P$1_P$1") (pintype "bidirectional"))
      (node (ref "SW1") (pin "P$2") (pinfunction "P$2_P$2") (pintype "bidirectional"))
    )
    (net (code "22") (name "Net-(U4-CT)") (class "Default")
      (node (ref "C7") (pin "1") (pinfunction "1_1") (pintype "passive"))
      (node (ref "U4") (pin "4") (pinfunction "CT_4") (pintype "bidirectional"))
    )
    (net (code "23") (name "Net-(U4-QOD)") (class "Default")
      (node (ref "R9") (pin "1") (pinfunction "1_1") (pintype "passive"))
      (node (ref "U4") (pin "5") (pinfunction "QOD_5") (pintype "bidirectional"))
    )
    (net (code "24") (name "Net-(U5-CT)") (class "Default")
      (node (ref "C6") (pin "1") (pinfunction "1_1") (pintype "passive"))
      (node (ref "U5") (pin "4") (pinfunction "CT_4") (pintype "bidirectional"))
    )
    (net (code "25") (name "Net-(U5-QOD)") (class "Default")
      (node (ref "R8") (pin "1") (pinfunction "1_1") (pintype "passive"))
      (node (ref "U5") (pin "5") (pinfunction "QOD_5") (pintype "bidirectional"))
    )
    (net (code "26") (name "Net-(U5-VOUT)") (class "Default")
      (node (ref "F1") (pin "1") (pinfunction "1_1") (pintype "bidirectional"))
      (node (ref "R8") (pin "2") (pinfunction "2_2") (pintype "passive"))
      (node (ref "U5") (pin "6") (pinfunction "VOUT_6") (pintype "power_in"))
    )
    (net (code "27") (name "Net-(U8-X1)") (class "Default")
      (node (ref "C12") (pin "1") (pinfunction "1_1") (pintype "passive"))
      (node (ref "U8") (pin "1") (pinfunction "X1_1") (pintype "input"))
      (node (ref "Y1") (pin "1") (pinfunction "1_1") (pintype "passive"))
    )
    (net (code "28") (name "Net-(U8-X2)") (class "Default")
      (node (ref "C11") (pin "1") (pinfunction "1_1") (pintype "passive"))
      (node (ref "U8") (pin "2") (pinfunction "X2_2") (pintype "output"))
      (node (ref "Y1") (pin "4") (pinfunction "4_4") (pintype "passive"))
    )
    (net (code "29") (name "RTC-INT") (class "Default")
      (node (ref "R1") (pin "2") (pinfunction "2_2") (pintype "passive"))
      (node (ref "U8") (pin "7") (pinfunction "MFP_7") (pintype "passive"))
    )
    (net (code "30") (name "RX") (class "Default")
      (node (ref "J7") (pin "4") (pinfunction "4_4") (pintype "passive"))
      (node (ref "P1") (pin "RX") (pinfunction "RX_RX") (pintype "bidirectional"))
    )
    (net (code "31") (name "SCK") (class "Default")
      (node (ref "J6") (pin "5") (pinfunction "5_5") (pintype "passive"))
      (node (ref "P1") (pin "SCK") (pinfunction "SCK_SCK") (pintype "bidirectional"))
    )
    (net (code "32") (name "SCL") (class "Default")
      (node (ref "ATTINY85") (pin "7") (pinfunction "PB2(SCK/ADC1)_7") (pintype "bidirectional"))
      (node (ref "G1") (pin "3") (pinfunction "3_3") (pintype "input"))
      (node (ref "ICSP") (pin "3") (pinfunction "SCK_3") (pintype "bidirectional"))
      (node (ref "J3") (pin "4") (pinfunction "4_4") (pintype "passive"))
      (node (ref "J4") (pin "4") (pinfunction "4_4") (pintype "passive"))
      (node (ref "J8") (pin "4") (pinfunction "4_4") (pintype "passive"))
      (node (ref "J9") (pin "4") (pinfunction "4_4") (pintype "passive"))
      (node (ref "P1") (pin "SCL") (pinfunction "SCL_SCL") (pintype "bidirectional"))
      (node (ref "R5") (pin "1") (pinfunction "1_1") (pintype "passive"))
      (node (ref "U2") (pin "6") (pinfunction "SCL_6") (pintype "input"))
      (node (ref "U8") (pin "6") (pinfunction "SCL_6") (pintype "input"))
    )
    (net (code "33") (name "SDA") (class "Default")
      (node (ref "ATTINY85") (pin "5") (pinfunction "PB0(MOSI)_5") (pintype "bidirectional"))
      (node (ref "G1") (pin "1") (pinfunction "1_1") (pintype "input"))
      (node (ref "ICSP") (pin "4") (pinfunction "MOSI_4") (pintype "bidirectional"))
      (node (ref "J3") (pin "3") (pinfunction "3_3") (pintype "passive"))
      (node (ref "J4") (pin "3") (pinfunction "3_3") (pintype "passive"))
      (node (ref "J8") (pin "3") (pinfunction "3_3") (pintype "passive"))
      (node (ref "J9") (pin "3") (pinfunction "3_3") (pintype "passive"))
      (node (ref "P1") (pin "SDA") (pinfunction "SDA_SDA") (pintype "bidirectional"))
      (node (ref "R4") (pin "1") (pinfunction "1_1") (pintype "passive"))
      (node (ref "U2") (pin "5") (pinfunction "SDA_5") (pintype "bidirectional"))
      (node (ref "U8") (pin "5") (pinfunction "SDA_5") (pintype "bidirectional"))
    )
    (net (code "34") (name "SS") (class "Default")
      (node (ref "J6") (pin "6") (pinfunction "6_6") (pintype "passive"))
      (node (ref "P1") (pin "A5") (pinfunction "A5_A5") (pintype "bidirectional"))
    )
    (net (code "35") (name "TEMP") (class "Default")
      (node (ref "P1") (pin "A4") (pinfunction "A4_A4") (pintype "bidirectional"))
      (node (ref "U1") (pin "1") (pinfunction "VOUT_1") (pintype "passive"))
    )
    (net (code "36") (name "TX") (class "Default")
      (node (ref "J7") (pin "3") (pinfunction "3_3") (pintype "passive"))
      (node (ref "P1") (pin "TX") (pinfunction "TX_TX") (pintype "bidirectional"))
    )
    (net (code "37") (name "USER-SW") (class "Default")
      (node (ref "C10") (pin "1") (pinfunction "1_1") (pintype "passive"))
      (node (ref "P1") (pin "D4") (pinfunction "D4_D4") (pintype "bidirectional"))
      (node (ref "R7") (pin "1") (pinfunction "1_1") (pintype "passive"))
    )
    (net (code "38") (name "VCC") (class "Default")
      (node (ref "C1") (pin "1") (pinfunction "1_1") (pintype "passive"))
      (node (ref "C2") (pin "1") (pinfunction "1_1") (pintype "passive"))
      (node (ref "D4") (pin "ANODE") (pinfunction "ANODE_ANODE") (pintype "bidirectional"))
      (node (ref "F2") (pin "1") (pinfunction "1_1") (pintype "bidirectional"))
      (node (ref "F3") (pin "1") (pinfunction "1_1") (pintype "bidirectional"))
      (node (ref "P1") (pin "3V3") (pinfunction "3V3_3V3") (pintype "bidirectional"))
      (node (ref "R4") (pin "2") (pinfunction "2_2") (pintype "passive"))
      (node (ref "R5") (pin "2") (pinfunction "2_2") (pintype "passive"))
      (node (ref "R6") (pin "2") (pinfunction "2_2") (pintype "passive"))
      (node (ref "U1") (pin "2") (pinfunction "+VS_2") (pintype "power_in"))
      (node (ref "U1") (pin "4") (pinfunction "~{SHTDWN}_4") (pintype "passive"))
      (node (ref "U2") (pin "8") (pinfunction "VDD_8") (pintype "power_in"))
      (node (ref "U8") (pin "8") (pinfunction "VCC_8") (pintype "power_in"))
    )
    (net (code "39") (name "VCC-EXT") (class "Default")
      (node (ref "F3") (pin "2") (pinfunction "2_2") (pintype "bidirectional"))
      (node (ref "J5") (pin "2") (pinfunction "2_2") (pintype "passive"))
      (node (ref "J6") (pin "2") (pinfunction "2_2") (pintype "passive"))
      (node (ref "J7") (pin "2") (pinfunction "2_2") (pintype "passive"))
      (node (ref "V3") (pin "2") (pinfunction "2_2") (pintype "passive"))
    )
    (net (code "40") (name "VCC-WDT") (class "Default")
      (node (ref "D4") (pin "CATHODE") (pinfunction "CATHODE_CATHODE") (pintype "bidirectional"))
      (node (ref "ICSP") (pin "2") (pinfunction "VCC_2") (pintype "power_in"))
      (node (ref "JP1") (pin "2") (pinfunction "2_2") (pintype "passive"))
      (node (ref "R3") (pin "2") (pinfunction "2_2") (pintype "passive"))
    )
    (net (code "41") (name "VCC2-EXT") (class "Default")
      (node (ref "F2") (pin "2") (pinfunction "2_2") (pintype "bidirectional"))
      (node (ref "J3") (pin "2") (pinfunction "2_2") (pintype "passive"))
      (node (ref "J4") (pin "2") (pinfunction "2_2") (pintype "passive"))
      (node (ref "J8") (pin "2") (pinfunction "2_2") (pintype "passive"))
      (node (ref "J9") (pin "2") (pinfunction "2_2") (pintype "passive"))
      (node (ref "V2") (pin "2") (pinfunction "2_2") (pintype "passive"))
    )
    (net (code "42") (name "VUSB") (class "Default")
      (node (ref "C8") (pin "P$1") (pinfunction "P$1_P$1") (pintype "passive"))
      (node (ref "F1") (pin "2") (pinfunction "2_2") (pintype "bidirectional"))
      (node (ref "P1") (pin "VUSB") (pinfunction "VUSB_VUSB") (pintype "bidirectional"))
      (node (ref "V1") (pin "2") (pinfunction "2_2") (pintype "passive"))
    )
    (net (code "43") (name "WAKE") (class "Default")
      (node (ref "ATTINY85") (pin "2") (pinfunction "PB3(ADC3)_2") (pintype "bidirectional"))
      (node (ref "P1") (pin "D8") (pinfunction "D8_D8") (pintype "bidirectional"))
    )
    (net (code "44") (name "unconnected-(J1-PAD1-PadNC1)") (class "Default")
      (node (ref "J1") (pin "NC1") (pinfunction "PAD1_NC1") (pintype "bidirectional"))
    )
    (net (code "45") (name "unconnected-(J1-PAD2-PadNC2)") (class "Default")
      (node (ref "J1") (pin "NC2") (pinfunction "PAD2_NC2") (pintype "bidirectional"))
    )
    (net (code "46") (name "unconnected-(J2-PAD1-PadNC1)") (class "Default")
      (node (ref "J2") (pin "NC1") (pinfunction "PAD1_NC1") (pintype "bidirectional"))
    )
    (net (code "47") (name "unconnected-(J2-PAD2-PadNC2)") (class "Default")
      (node (ref "J2") (pin "NC2") (pinfunction "PAD2_NC2") (pintype "bidirectional"))
    )
    (net (code "48") (name "unconnected-(P1-PadD7)") (class "Default")
      (node (ref "P1") (pin "D7") (pinfunction "D7_D7") (pintype "bidirectional"))
    )
    (net (code "49") (name "unconnected-(P1-PadNC)") (class "Default")
      (node (ref "P1") (pin "NC") (pinfunction "NC_NC") (pintype "bidirectional"))
    )
    (net (code "50") (name "unconnected-(U1-NC-Pad3)") (class "Default")
      (node (ref "U1") (pin "3") (pinfunction "NC_3") (pintype "passive"))
    )
    (net (code "51") (name "~{RST}") (class "Default")
      (node (ref "ATTINY85") (pin "6") (pinfunction "PB1(MISO)_6") (pintype "bidirectional"))
      (node (ref "ICSP") (pin "1") (pinfunction "MISO_1") (pintype "bidirectional"))
      (node (ref "P1") (pin "RST") (pinfunction "~{RST}_RST") (pintype "bidirectional"))
    )
    (net (code "52") (name "~{TINY-RST}") (class "Default")
      (node (ref "ATTINY85") (pin "1") (pinfunction "PB5(NRES)_1") (pintype "bidirectional"))
      (node (ref "ICSP") (pin "5") (pinfunction "~{RESET}_5") (pintype "input"))
      (node (ref "R3") (pin "1") (pinfunction "1_1") (pintype "passive"))
    )
  )
)
